# quad_decay_v1_0_1_pnl.net
KiCad netlist of a schematic drawn in EAGLE
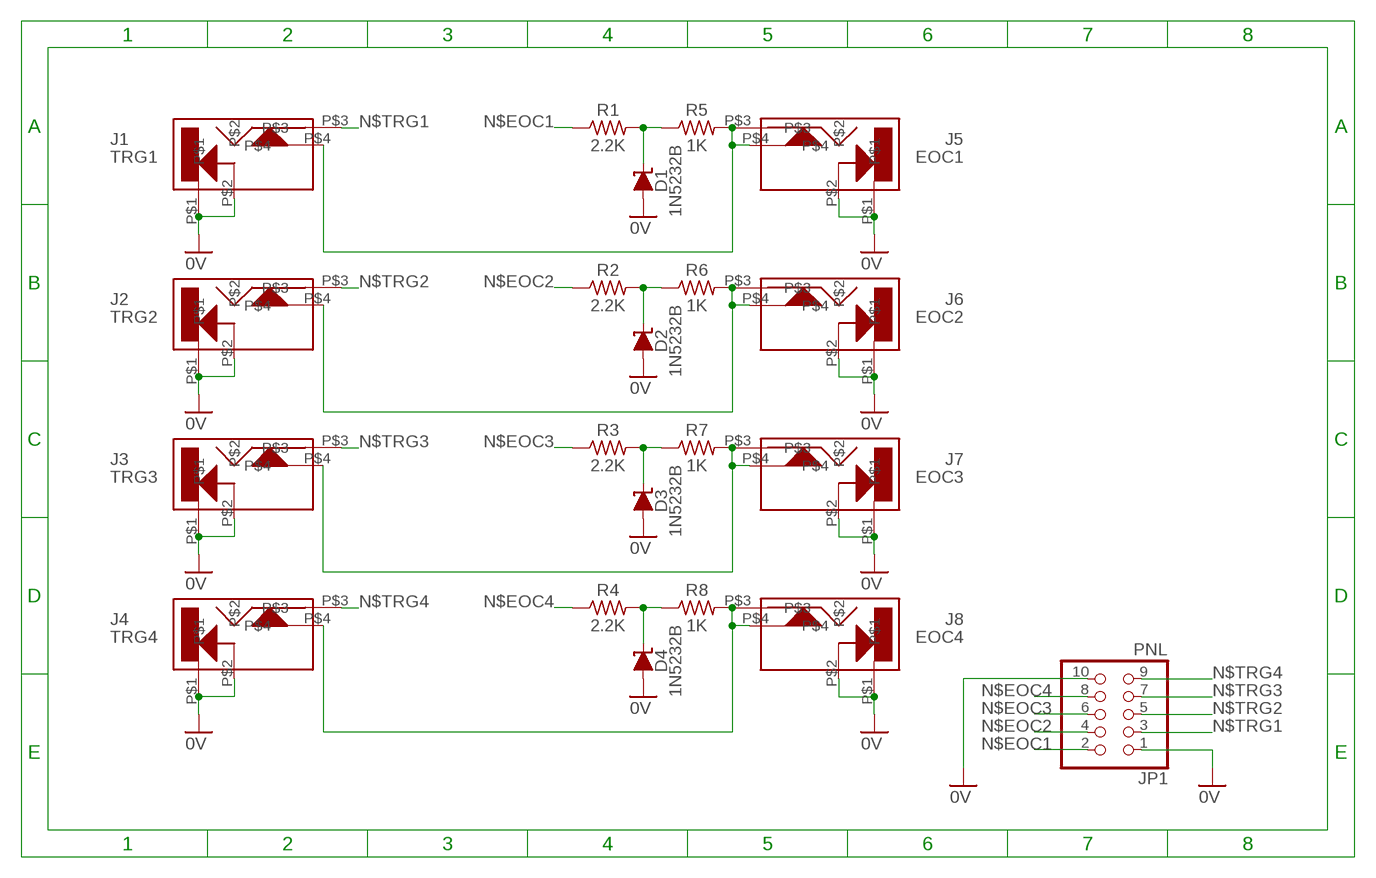
[diagram p0: schematic, sheet 1]

(export (version "E")
  (design (tool "Eeschema 10.0.6"))
  (components
    (comp (ref "D1")
      (value "1N5232B")
      (footprint "eagle-import:DO34-5")
      (libsource (lib "eagle-import") (part "1N5232B"))
    )
    (comp (ref "D2")
      (value "1N5232B")
      (footprint "eagle-import:DO34-5")
      (libsource (lib "eagle-import") (part "1N5232B"))
    )
    (comp (ref "D3")
      (value "1N5232B")
      (footprint "eagle-import:DO34-5")
      (libsource (lib "eagle-import") (part "1N5232B"))
    )
    (comp (ref "D4")
      (value "1N5232B")
      (footprint "eagle-import:DO34-5")
      (libsource (lib "eagle-import") (part "1N5232B"))
    )
    (comp (ref "J1")
      (value "TRG1")
      (footprint "eagle-import:CL1384")
      (libsource (lib "eagle-import") (part "CL1384"))
    )
    (comp (ref "J2")
      (value "TRG2")
      (footprint "eagle-import:CL1384")
      (libsource (lib "eagle-import") (part "CL1384"))
    )
    (comp (ref "J3")
      (value "TRG3")
      (footprint "eagle-import:CL1384")
      (libsource (lib "eagle-import") (part "CL1384"))
    )
    (comp (ref "J4")
      (value "TRG4")
      (footprint "eagle-import:CL1384")
      (libsource (lib "eagle-import") (part "CL1384"))
    )
    (comp (ref "J5")
      (value "EOC1")
      (footprint "eagle-import:CL1384")
      (libsource (lib "eagle-import") (part "CL1384"))
    )
    (comp (ref "J6")
      (value "EOC2")
      (footprint "eagle-import:CL1384")
      (libsource (lib "eagle-import") (part "CL1384"))
    )
    (comp (ref "J7")
      (value "EOC3")
      (footprint "eagle-import:CL1384")
      (libsource (lib "eagle-import") (part "CL1384"))
    )
    (comp (ref "J8")
      (value "EOC4")
      (footprint "eagle-import:CL1384")
      (libsource (lib "eagle-import") (part "CL1384"))
    )
    (comp (ref "JP1")
      (value "PNL")
      (footprint "eagle-import:2X05")
      (libsource (lib "eagle-import") (part "PINHD-2X5"))
    )
    (comp (ref "R1")
      (value "2.2K")
      (footprint "eagle-import:0207_7")
      (libsource (lib "eagle-import") (part "R"))
    )
    (comp (ref "R2")
      (value "2.2K")
      (footprint "eagle-import:0207_7")
      (libsource (lib "eagle-import") (part "R"))
    )
    (comp (ref "R3")
      (value "2.2K")
      (footprint "eagle-import:0207_7")
      (libsource (lib "eagle-import") (part "R"))
    )
    (comp (ref "R4")
      (value "2.2K")
      (footprint "eagle-import:0207_7")
      (libsource (lib "eagle-import") (part "R"))
    )
    (comp (ref "R5")
      (value "1K")
      (footprint "eagle-import:0207_7")
      (libsource (lib "eagle-import") (part "R"))
    )
    (comp (ref "R6")
      (value "1K")
      (footprint "eagle-import:0207_7")
      (libsource (lib "eagle-import") (part "R"))
    )
    (comp (ref "R7")
      (value "1K")
      (footprint "eagle-import:0207_7")
      (libsource (lib "eagle-import") (part "R"))
    )
    (comp (ref "R8")
      (value "1K")
      (footprint "eagle-import:0207_7")
      (libsource (lib "eagle-import") (part "R"))
    )
  )
  (nets
    (net (code "1") (name "/N$EOC1") (class "Default")
      (node (ref "JP1") (pin "2") (pinfunction "2_2") (pintype "passive"))
      (node (ref "R1") (pin "1") (pinfunction "1_1") (pintype "passive"))
    )
    (net (code "2") (name "/N$EOC2") (class "Default")
      (node (ref "JP1") (pin "4") (pinfunction "4_4") (pintype "passive"))
      (node (ref "R2") (pin "1") (pinfunction "1_1") (pintype "passive"))
    )
    (net (code "3") (name "/N$EOC3") (class "Default")
      (node (ref "JP1") (pin "6") (pinfunction "6_6") (pintype "passive"))
      (node (ref "R3") (pin "1") (pinfunction "1_1") (pintype "passive"))
    )
    (net (code "4") (name "/N$EOC4") (class "Default")
      (node (ref "JP1") (pin "8") (pinfunction "8_8") (pintype "passive"))
      (node (ref "R4") (pin "1") (pinfunction "1_1") (pintype "passive"))
    )
    (net (code "5") (name "/N$TRG1") (class "Default")
      (node (ref "J1") (pin "P$3") (pinfunction "P$3_P$3") (pintype "bidirectional"))
      (node (ref "JP1") (pin "3") (pinfunction "3_3") (pintype "passive"))
    )
    (net (code "6") (name "/N$TRG2") (class "Default")
      (node (ref "J2") (pin "P$3") (pinfunction "P$3_P$3") (pintype "bidirectional"))
      (node (ref "JP1") (pin "5") (pinfunction "5_5") (pintype "passive"))
    )
    (net (code "7") (name "/N$TRG3") (class "Default")
      (node (ref "J3") (pin "P$3") (pinfunction "P$3_P$3") (pintype "bidirectional"))
      (node (ref "JP1") (pin "7") (pinfunction "7_7") (pintype "passive"))
    )
    (net (code "8") (name "/N$TRG4") (class "Default")
      (node (ref "J4") (pin "P$3") (pinfunction "P$3_P$3") (pintype "bidirectional"))
      (node (ref "JP1") (pin "9") (pinfunction "9_9") (pintype "passive"))
    )
    (net (code "9") (name "0V") (class "Default")
      (node (ref "D1") (pin "A") (pinfunction "A_A") (pintype "passive"))
      (node (ref "D2") (pin "A") (pinfunction "A_A") (pintype "passive"))
      (node (ref "D3") (pin "A") (pinfunction "A_A") (pintype "passive"))
      (node (ref "D4") (pin "A") (pinfunction "A_A") (pintype "passive"))
      (node (ref "J1") (pin "P$1") (pinfunction "P$1_P$1") (pintype "bidirectional"))
      (node (ref "J1") (pin "P$2") (pinfunction "P$2_P$2") (pintype "bidirectional"))
      (node (ref "J2") (pin "P$1") (pinfunction "P$1_P$1") (pintype "bidirectional"))
      (node (ref "J2") (pin "P$2") (pinfunction "P$2_P$2") (pintype "bidirectional"))
      (node (ref "J3") (pin "P$1") (pinfunction "P$1_P$1") (pintype "bidirectional"))
      (node (ref "J3") (pin "P$2") (pinfunction "P$2_P$2") (pintype "bidirectional"))
      (node (ref "J4") (pin "P$1") (pinfunction "P$1_P$1") (pintype "bidirectional"))
      (node (ref "J4") (pin "P$2") (pinfunction "P$2_P$2") (pintype "bidirectional"))
      (node (ref "J5") (pin "P$1") (pinfunction "P$1_P$1") (pintype "bidirectional"))
      (node (ref "J5") (pin "P$2") (pinfunction "P$2_P$2") (pintype "bidirectional"))
      (node (ref "J6") (pin "P$1") (pinfunction "P$1_P$1") (pintype "bidirectional"))
      (node (ref "J6") (pin "P$2") (pinfunction "P$2_P$2") (pintype "bidirectional"))
      (node (ref "J7") (pin "P$1") (pinfunction "P$1_P$1") (pintype "bidirectional"))
      (node (ref "J7") (pin "P$2") (pinfunction "P$2_P$2") (pintype "bidirectional"))
      (node (ref "J8") (pin "P$1") (pinfunction "P$1_P$1") (pintype "bidirectional"))
      (node (ref "J8") (pin "P$2") (pinfunction "P$2_P$2") (pintype "bidirectional"))
      (node (ref "JP1") (pin "1") (pinfunction "1_1") (pintype "passive"))
      (node (ref "JP1") (pin "10") (pinfunction "10_10") (pintype "passive"))
    )
    (net (code "10") (name "Net-(D1-PadC)") (class "Default")
      (node (ref "D1") (pin "C") (pinfunction "C_C") (pintype "passive"))
      (node (ref "R1") (pin "2") (pinfunction "2_2") (pintype "passive"))
      (node (ref "R5") (pin "1") (pinfunction "1_1") (pintype "passive"))
    )
    (net (code "11") (name "Net-(D2-PadC)") (class "Default")
      (node (ref "D2") (pin "C") (pinfunction "C_C") (pintype "passive"))
      (node (ref "R2") (pin "2") (pinfunction "2_2") (pintype "passive"))
      (node (ref "R6") (pin "1") (pinfunction "1_1") (pintype "passive"))
    )
    (net (code "12") (name "Net-(D3-PadC)") (class "Default")
      (node (ref "D3") (pin "C") (pinfunction "C_C") (pintype "passive"))
      (node (ref "R3") (pin "2") (pinfunction "2_2") (pintype "passive"))
      (node (ref "R7") (pin "1") (pinfunction "1_1") (pintype "passive"))
    )
    (net (code "13") (name "Net-(D4-PadC)") (class "Default")
      (node (ref "D4") (pin "C") (pinfunction "C_C") (pintype "passive"))
      (node (ref "R4") (pin "2") (pinfunction "2_2") (pintype "passive"))
      (node (ref "R8") (pin "1") (pinfunction "1_1") (pintype "passive"))
    )
    (net (code "14") (name "Net-(J1-PadP$4)") (class "Default")
      (node (ref "J1") (pin "P$4") (pinfunction "P$4_P$4") (pintype "bidirectional"))
      (node (ref "J5") (pin "P$3") (pinfunction "P$3_P$3") (pintype "bidirectional"))
      (node (ref "J5") (pin "P$4") (pinfunction "P$4_P$4") (pintype "bidirectional"))
      (node (ref "R5") (pin "2") (pinfunction "2_2") (pintype "passive"))
    )
    (net (code "15") (name "Net-(J2-PadP$4)") (class "Default")
      (node (ref "J2") (pin "P$4") (pinfunction "P$4_P$4") (pintype "bidirectional"))
      (node (ref "J6") (pin "P$3") (pinfunction "P$3_P$3") (pintype "bidirectional"))
      (node (ref "J6") (pin "P$4") (pinfunction "P$4_P$4") (pintype "bidirectional"))
      (node (ref "R6") (pin "2") (pinfunction "2_2") (pintype "passive"))
    )
    (net (code "16") (name "Net-(J3-PadP$4)") (class "Default")
      (node (ref "J3") (pin "P$4") (pinfunction "P$4_P$4") (pintype "bidirectional"))
      (node (ref "J7") (pin "P$3") (pinfunction "P$3_P$3") (pintype "bidirectional"))
      (node (ref "J7") (pin "P$4") (pinfunction "P$4_P$4") (pintype "bidirectional"))
      (node (ref "R7") (pin "2") (pinfunction "2_2") (pintype "passive"))
    )
    (net (code "17") (name "Net-(J4-PadP$4)") (class "Default")
      (node (ref "J4") (pin "P$4") (pinfunction "P$4_P$4") (pintype "bidirectional"))
      (node (ref "J8") (pin "P$3") (pinfunction "P$3_P$3") (pintype "bidirectional"))
      (node (ref "J8") (pin "P$4") (pinfunction "P$4_P$4") (pintype "bidirectional"))
      (node (ref "R8") (pin "2") (pinfunction "2_2") (pintype "passive"))
    )
  )
)
